# SHIFT_LEFT_RIGHT_1.net
KiCad netlist of a schematic drawn in EAGLE
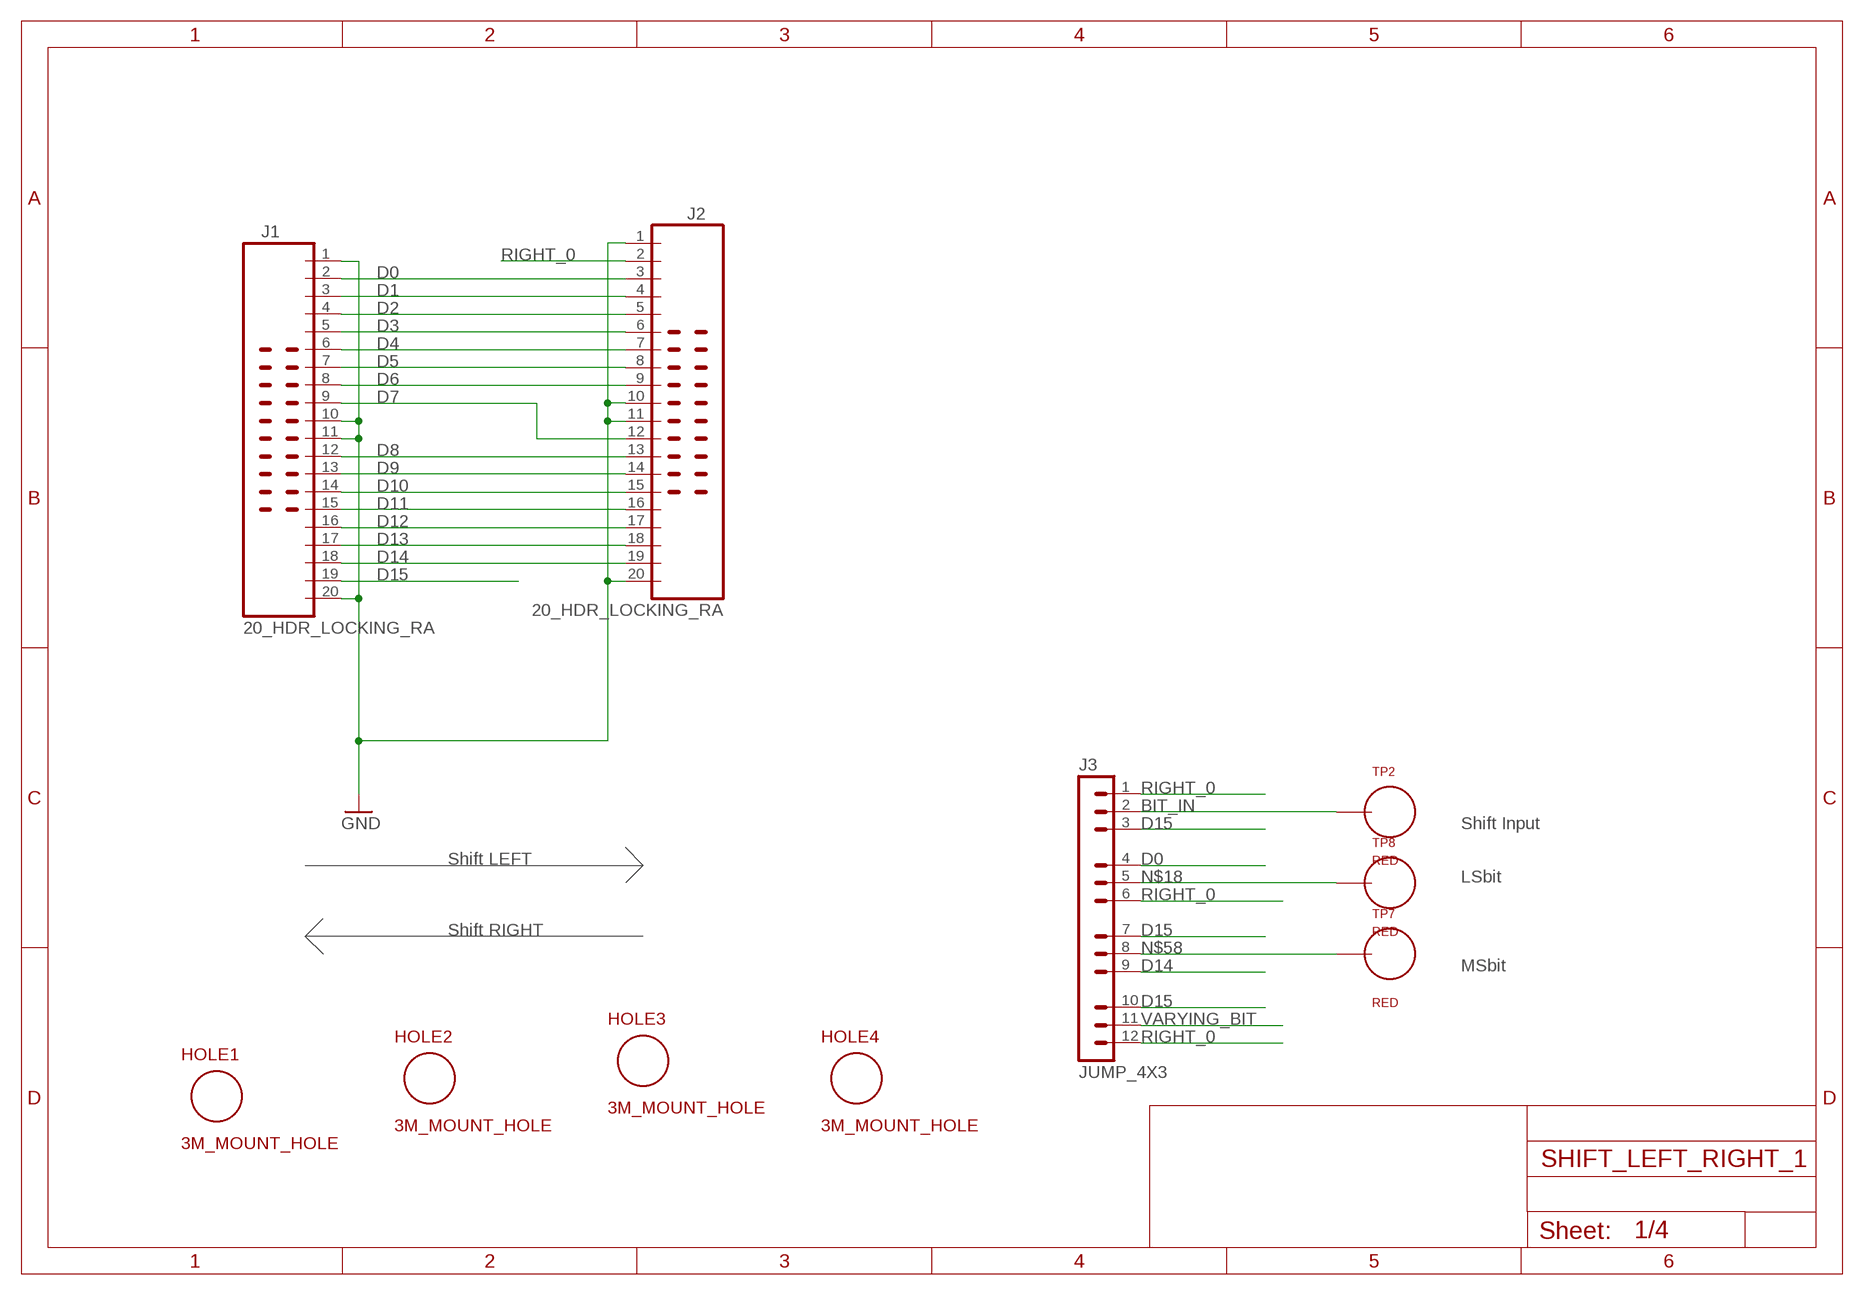
[diagram p0: schematic, sheet 1]
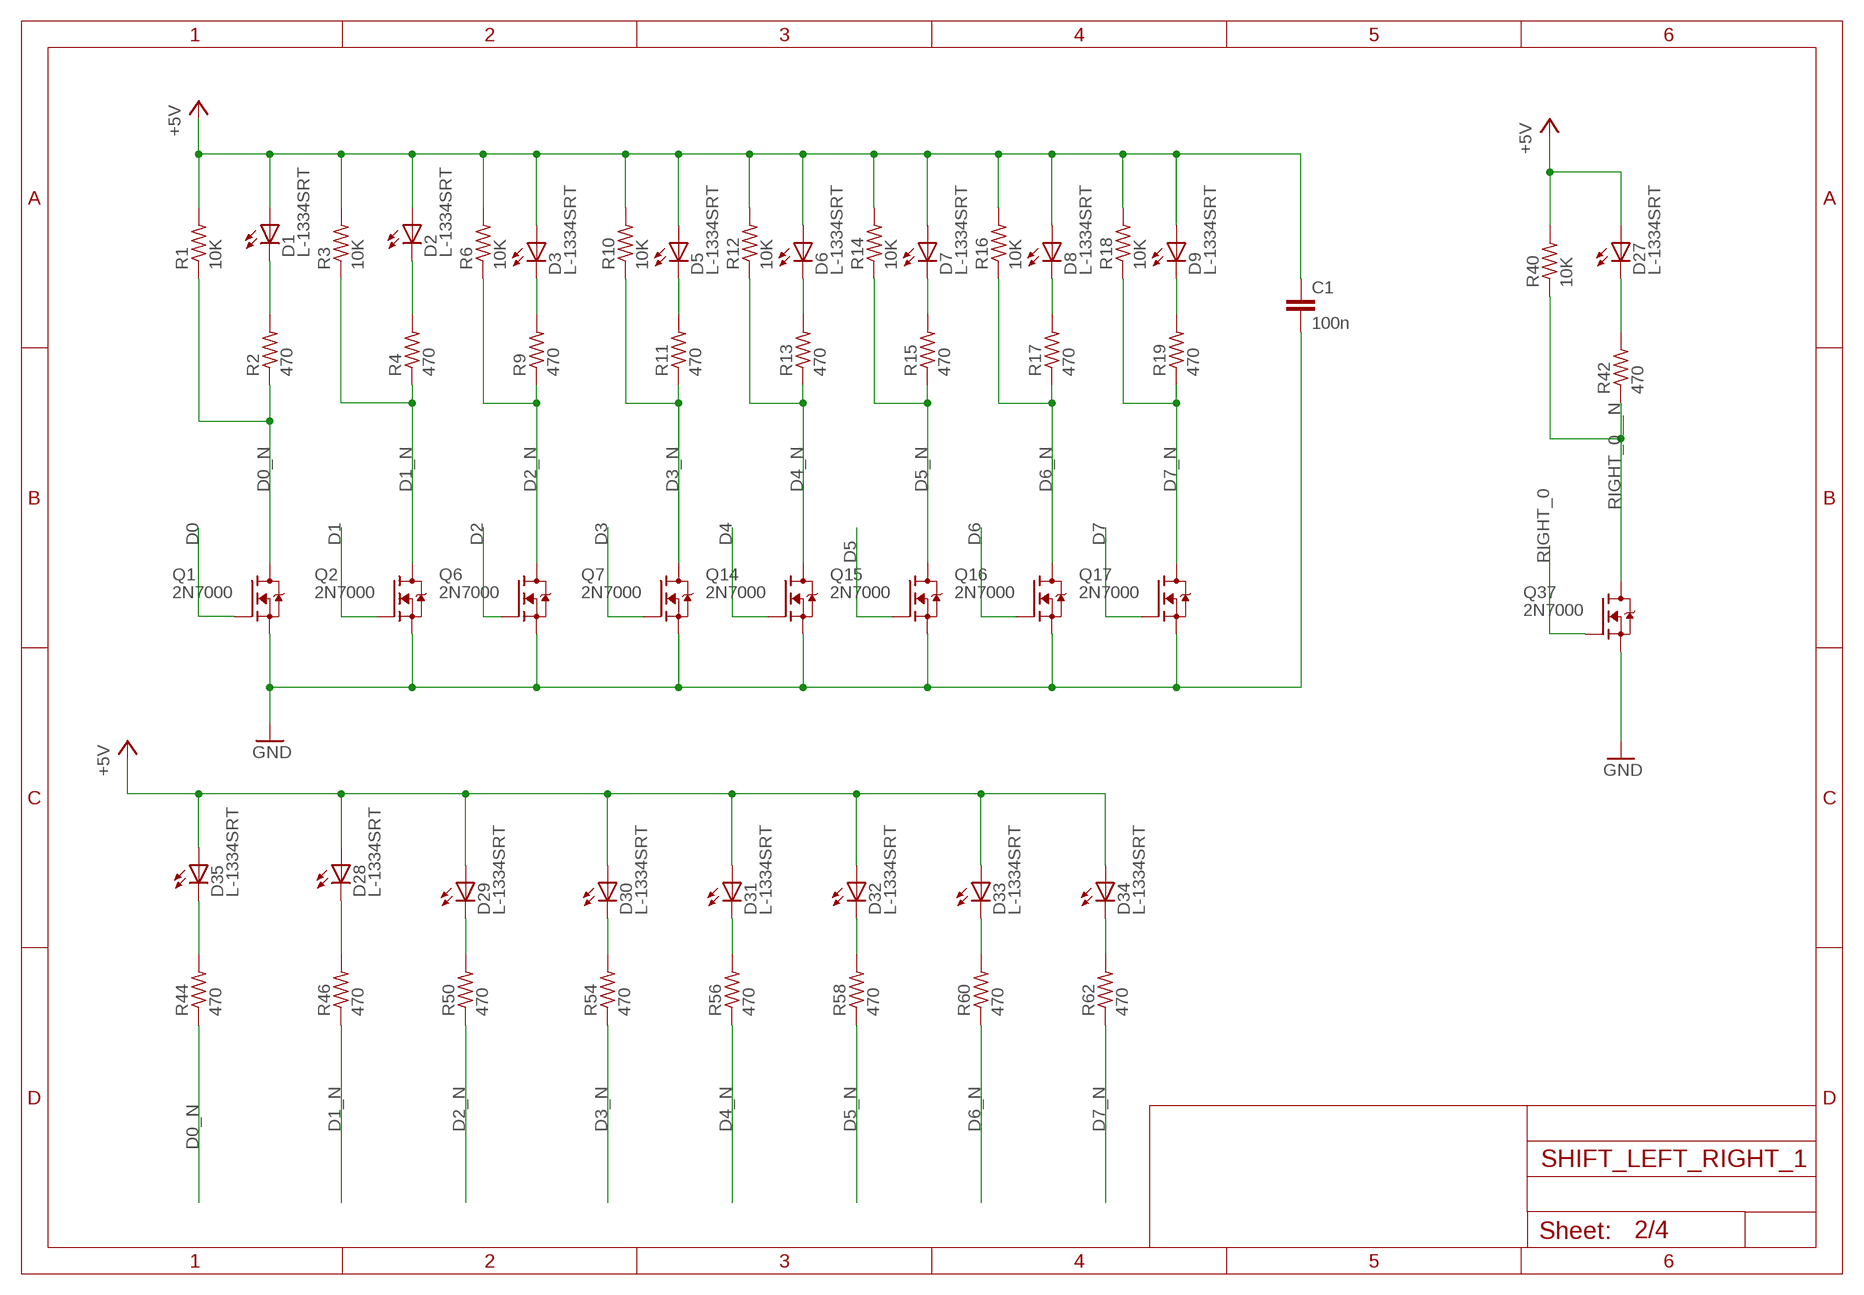
[diagram p1: schematic, sheet 2]
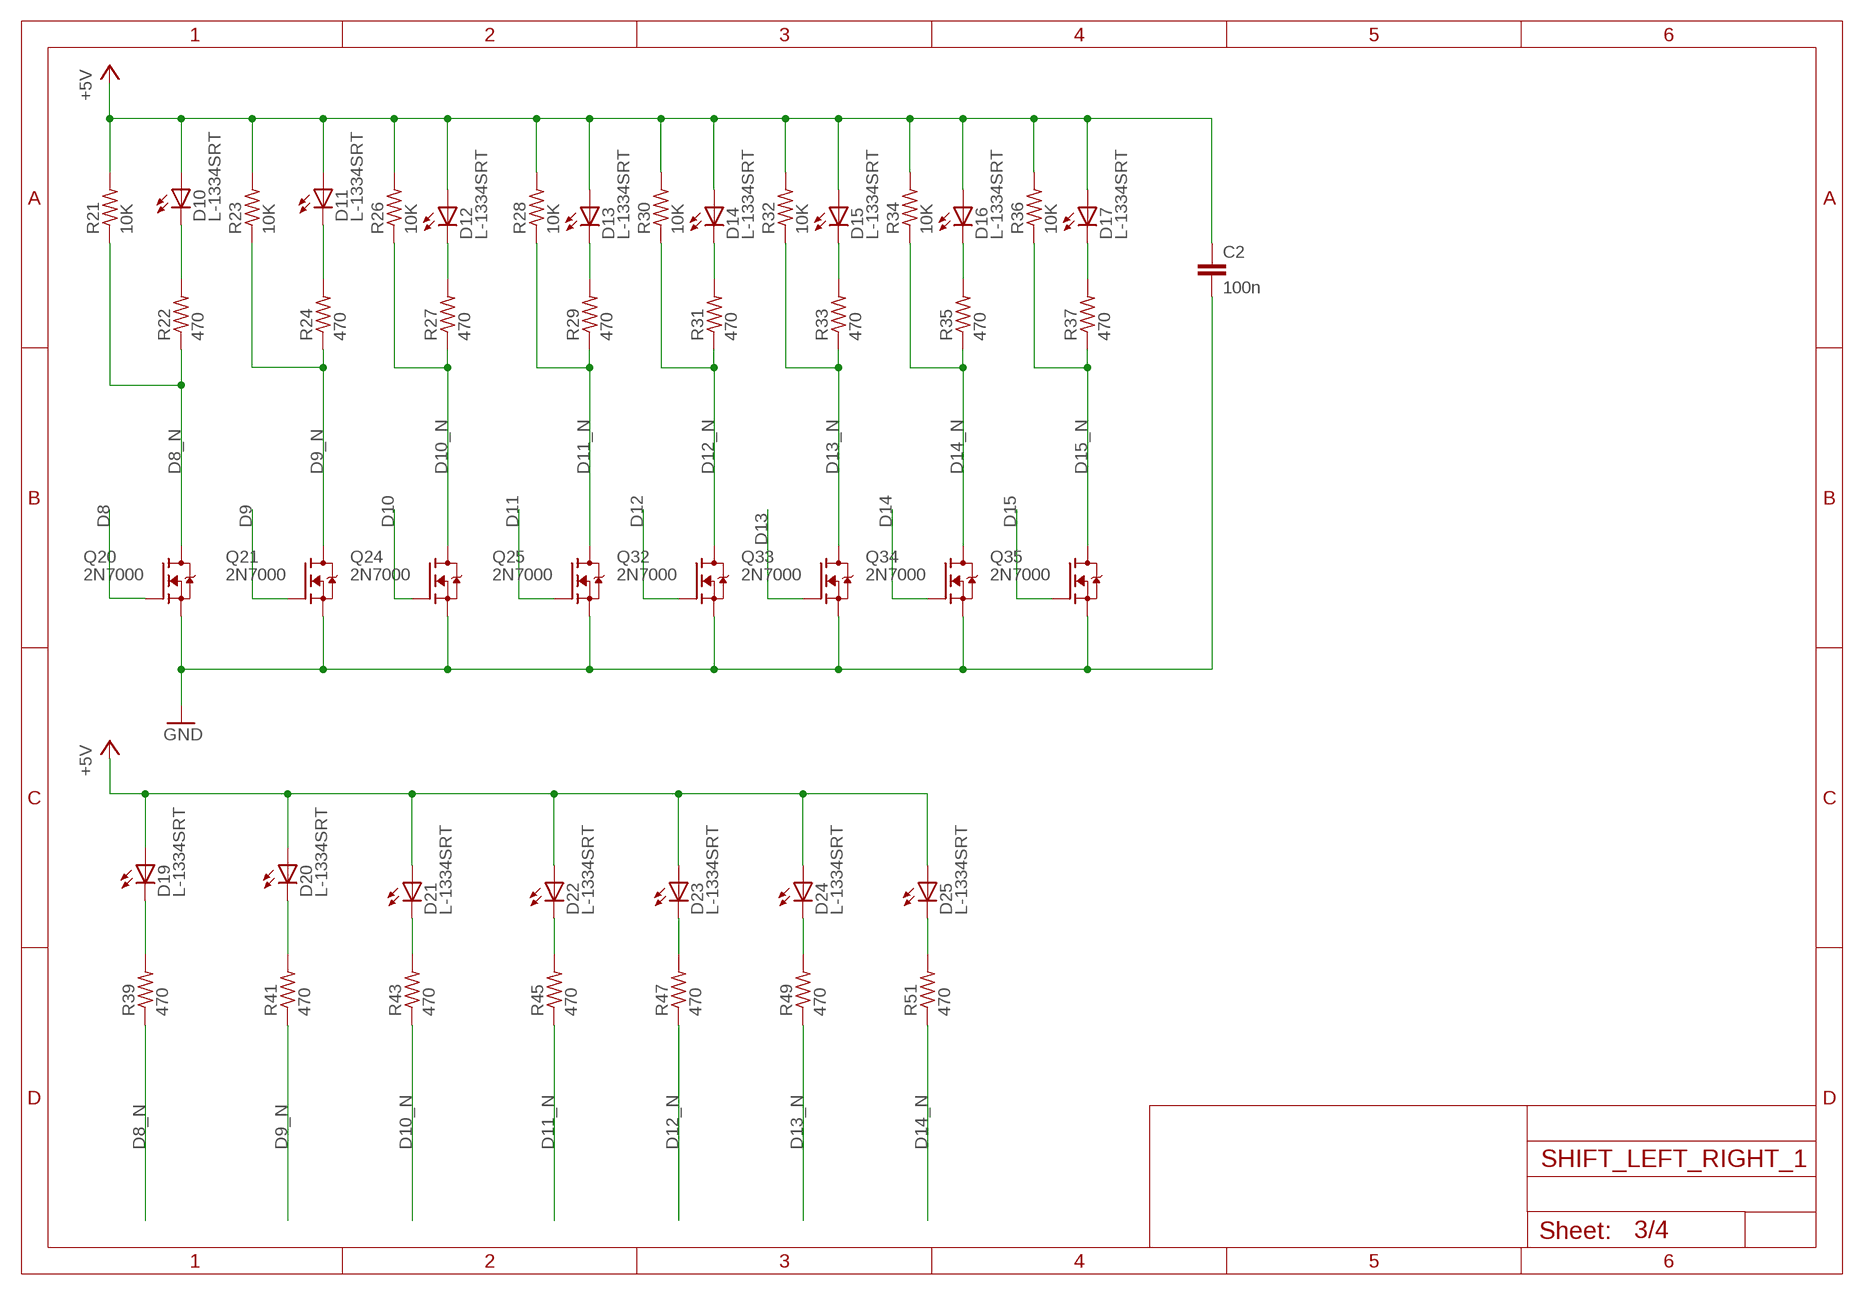
[diagram p2: schematic, sheet 3]
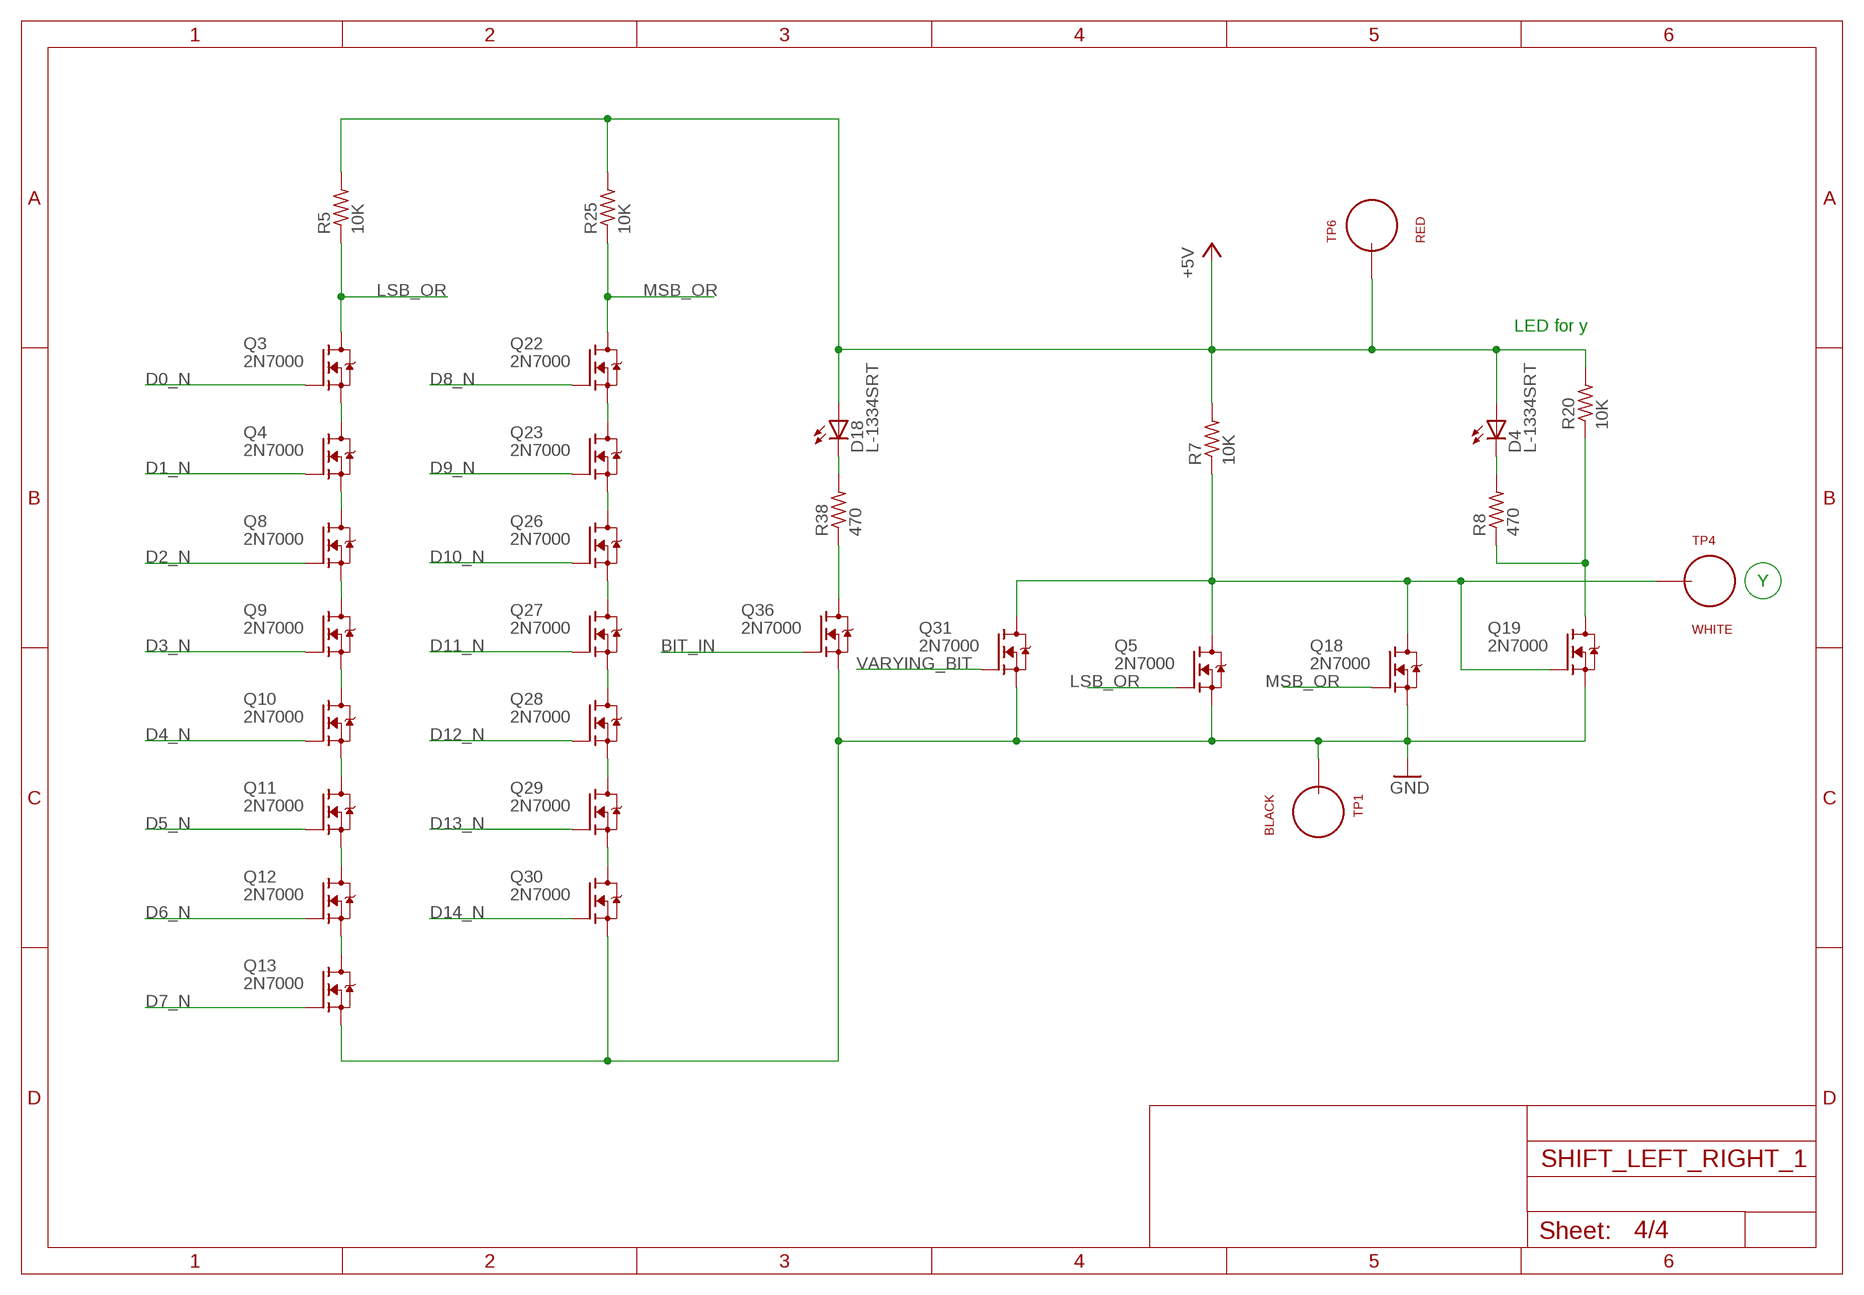
[diagram p3: schematic, sheet 4]

(export (version "E")
  (design (tool "Eeschema 10.0.6"))
  (components
    (comp (ref "C2")
      (value "100n")
      (footprint "eagle-import:CAP_P2INCH")
      (libsource (lib "eagle-import") (part "C_P2INCH"))
    )
    (comp (ref "D10")
      (value "L-1334SRT")
      (footprint "eagle-import:LED3MM")
      (libsource (lib "eagle-import") (part "L-1334SRT"))
    )
    (comp (ref "D11")
      (value "L-1334SRT")
      (footprint "eagle-import:LED3MM")
      (libsource (lib "eagle-import") (part "L-1334SRT"))
    )
    (comp (ref "D12")
      (value "L-1334SRT")
      (footprint "eagle-import:LED3MM")
      (libsource (lib "eagle-import") (part "L-1334SRT"))
    )
    (comp (ref "D13")
      (value "L-1334SRT")
      (footprint "eagle-import:LED3MM")
      (libsource (lib "eagle-import") (part "L-1334SRT"))
    )
    (comp (ref "D14")
      (value "L-1334SRT")
      (footprint "eagle-import:LED3MM")
      (libsource (lib "eagle-import") (part "L-1334SRT"))
    )
    (comp (ref "D15")
      (value "L-1334SRT")
      (footprint "eagle-import:LED3MM")
      (libsource (lib "eagle-import") (part "L-1334SRT"))
    )
    (comp (ref "D16")
      (value "L-1334SRT")
      (footprint "eagle-import:LED3MM")
      (libsource (lib "eagle-import") (part "L-1334SRT"))
    )
    (comp (ref "D17")
      (value "L-1334SRT")
      (footprint "eagle-import:LED3MM")
      (libsource (lib "eagle-import") (part "L-1334SRT"))
    )
    (comp (ref "D19")
      (value "L-1334SRT")
      (footprint "eagle-import:LED3MM")
      (libsource (lib "eagle-import") (part "L-1334SRT"))
    )
    (comp (ref "D20")
      (value "L-1334SRT")
      (footprint "eagle-import:LED3MM")
      (libsource (lib "eagle-import") (part "L-1334SRT"))
    )
    (comp (ref "D21")
      (value "L-1334SRT")
      (footprint "eagle-import:LED3MM")
      (libsource (lib "eagle-import") (part "L-1334SRT"))
    )
    (comp (ref "D22")
      (value "L-1334SRT")
      (footprint "eagle-import:LED3MM")
      (libsource (lib "eagle-import") (part "L-1334SRT"))
    )
    (comp (ref "D23")
      (value "L-1334SRT")
      (footprint "eagle-import:LED3MM")
      (libsource (lib "eagle-import") (part "L-1334SRT"))
    )
    (comp (ref "D24")
      (value "L-1334SRT")
      (footprint "eagle-import:LED3MM")
      (libsource (lib "eagle-import") (part "L-1334SRT"))
    )
    (comp (ref "D25")
      (value "L-1334SRT")
      (footprint "eagle-import:LED3MM")
      (libsource (lib "eagle-import") (part "L-1334SRT"))
    )
    (comp (ref "Q20")
      (value "2N7000")
      (footprint "eagle-import:TO92-DGS")
      (libsource (lib "eagle-import") (part "2N7000"))
    )
    (comp (ref "Q21")
      (value "2N7000")
      (footprint "eagle-import:TO92-DGS")
      (libsource (lib "eagle-import") (part "2N7000"))
    )
    (comp (ref "Q24")
      (value "2N7000")
      (footprint "eagle-import:TO92-DGS")
      (libsource (lib "eagle-import") (part "2N7000"))
    )
    (comp (ref "Q25")
      (value "2N7000")
      (footprint "eagle-import:TO92-DGS")
      (libsource (lib "eagle-import") (part "2N7000"))
    )
    (comp (ref "Q32")
      (value "2N7000")
      (footprint "eagle-import:TO92-DGS")
      (libsource (lib "eagle-import") (part "2N7000"))
    )
    (comp (ref "Q33")
      (value "2N7000")
      (footprint "eagle-import:TO92-DGS")
      (libsource (lib "eagle-import") (part "2N7000"))
    )
    (comp (ref "Q34")
      (value "2N7000")
      (footprint "eagle-import:TO92-DGS")
      (libsource (lib "eagle-import") (part "2N7000"))
    )
    (comp (ref "Q35")
      (value "2N7000")
      (footprint "eagle-import:TO92-DGS")
      (libsource (lib "eagle-import") (part "2N7000"))
    )
    (comp (ref "R21")
      (value "10K")
      (footprint "eagle-import:R_P2INCH")
      (libsource (lib "eagle-import") (part "R_P2INCH"))
    )
    (comp (ref "R22")
      (value "470")
      (footprint "eagle-import:R_P2INCH")
      (libsource (lib "eagle-import") (part "R_P2INCH"))
    )
    (comp (ref "R23")
      (value "10K")
      (footprint "eagle-import:R_P2INCH")
      (libsource (lib "eagle-import") (part "R_P2INCH"))
    )
    (comp (ref "R24")
      (value "470")
      (footprint "eagle-import:R_P2INCH")
      (libsource (lib "eagle-import") (part "R_P2INCH"))
    )
    (comp (ref "R26")
      (value "10K")
      (footprint "eagle-import:R_P2INCH")
      (libsource (lib "eagle-import") (part "R_P2INCH"))
    )
    (comp (ref "R27")
      (value "470")
      (footprint "eagle-import:R_P2INCH")
      (libsource (lib "eagle-import") (part "R_P2INCH"))
    )
    (comp (ref "R28")
      (value "10K")
      (footprint "eagle-import:R_P2INCH")
      (libsource (lib "eagle-import") (part "R_P2INCH"))
    )
    (comp (ref "R29")
      (value "470")
      (footprint "eagle-import:R_P2INCH")
      (libsource (lib "eagle-import") (part "R_P2INCH"))
    )
    (comp (ref "R30")
      (value "10K")
      (footprint "eagle-import:R_P2INCH")
      (libsource (lib "eagle-import") (part "R_P2INCH"))
    )
    (comp (ref "R31")
      (value "470")
      (footprint "eagle-import:R_P2INCH")
      (libsource (lib "eagle-import") (part "R_P2INCH"))
    )
    (comp (ref "R32")
      (value "10K")
      (footprint "eagle-import:R_P2INCH")
      (libsource (lib "eagle-import") (part "R_P2INCH"))
    )
    (comp (ref "R33")
      (value "470")
      (footprint "eagle-import:R_P2INCH")
      (libsource (lib "eagle-import") (part "R_P2INCH"))
    )
    (comp (ref "R34")
      (value "10K")
      (footprint "eagle-import:R_P2INCH")
      (libsource (lib "eagle-import") (part "R_P2INCH"))
    )
    (comp (ref "R35")
      (value "470")
      (footprint "eagle-import:R_P2INCH")
      (libsource (lib "eagle-import") (part "R_P2INCH"))
    )
    (comp (ref "R36")
      (value "10K")
      (footprint "eagle-import:R_P2INCH")
      (libsource (lib "eagle-import") (part "R_P2INCH"))
    )
    (comp (ref "R37")
      (value "470")
      (footprint "eagle-import:R_P2INCH")
      (libsource (lib "eagle-import") (part "R_P2INCH"))
    )
    (comp (ref "R39")
      (value "470")
      (footprint "eagle-import:R_P2INCH")
      (libsource (lib "eagle-import") (part "R_P2INCH"))
    )
    (comp (ref "R41")
      (value "470")
      (footprint "eagle-import:R_P2INCH")
      (libsource (lib "eagle-import") (part "R_P2INCH"))
    )
    (comp (ref "R43")
      (value "470")
      (footprint "eagle-import:R_P2INCH")
      (libsource (lib "eagle-import") (part "R_P2INCH"))
    )
    (comp (ref "R45")
      (value "470")
      (footprint "eagle-import:R_P2INCH")
      (libsource (lib "eagle-import") (part "R_P2INCH"))
    )
    (comp (ref "R47")
      (value "470")
      (footprint "eagle-import:R_P2INCH")
      (libsource (lib "eagle-import") (part "R_P2INCH"))
    )
    (comp (ref "R49")
      (value "470")
      (footprint "eagle-import:R_P2INCH")
      (libsource (lib "eagle-import") (part "R_P2INCH"))
    )
    (comp (ref "R51")
      (value "470")
      (footprint "eagle-import:R_P2INCH")
      (libsource (lib "eagle-import") (part "R_P2INCH"))
    )
    (comp (ref "C1")
      (value "100n")
      (footprint "eagle-import:CAP_P2INCH")
      (libsource (lib "eagle-import") (part "C_P2INCH"))
    )
    (comp (ref "D1")
      (value "L-1334SRT")
      (footprint "eagle-import:LED3MM")
      (libsource (lib "eagle-import") (part "L-1334SRT"))
    )
    (comp (ref "D2")
      (value "L-1334SRT")
      (footprint "eagle-import:LED3MM")
      (libsource (lib "eagle-import") (part "L-1334SRT"))
    )
    (comp (ref "D3")
      (value "L-1334SRT")
      (footprint "eagle-import:LED3MM")
      (libsource (lib "eagle-import") (part "L-1334SRT"))
    )
    (comp (ref "D5")
      (value "L-1334SRT")
      (footprint "eagle-import:LED3MM")
      (libsource (lib "eagle-import") (part "L-1334SRT"))
    )
    (comp (ref "D6")
      (value "L-1334SRT")
      (footprint "eagle-import:LED3MM")
      (libsource (lib "eagle-import") (part "L-1334SRT"))
    )
    (comp (ref "D7")
      (value "L-1334SRT")
      (footprint "eagle-import:LED3MM")
      (libsource (lib "eagle-import") (part "L-1334SRT"))
    )
    (comp (ref "D8")
      (value "L-1334SRT")
      (footprint "eagle-import:LED3MM")
      (libsource (lib "eagle-import") (part "L-1334SRT"))
    )
    (comp (ref "D9")
      (value "L-1334SRT")
      (footprint "eagle-import:LED3MM")
      (libsource (lib "eagle-import") (part "L-1334SRT"))
    )
    (comp (ref "D27")
      (value "L-1334SRT")
      (footprint "eagle-import:LED3MM")
      (libsource (lib "eagle-import") (part "L-1334SRT"))
    )
    (comp (ref "D28")
      (value "L-1334SRT")
      (footprint "eagle-import:LED3MM")
      (libsource (lib "eagle-import") (part "L-1334SRT"))
    )
    (comp (ref "D29")
      (value "L-1334SRT")
      (footprint "eagle-import:LED3MM")
      (libsource (lib "eagle-import") (part "L-1334SRT"))
    )
    (comp (ref "D30")
      (value "L-1334SRT")
      (footprint "eagle-import:LED3MM")
      (libsource (lib "eagle-import") (part "L-1334SRT"))
    )
    (comp (ref "D31")
      (value "L-1334SRT")
      (footprint "eagle-import:LED3MM")
      (libsource (lib "eagle-import") (part "L-1334SRT"))
    )
    (comp (ref "D32")
      (value "L-1334SRT")
      (footprint "eagle-import:LED3MM")
      (libsource (lib "eagle-import") (part "L-1334SRT"))
    )
    (comp (ref "D33")
      (value "L-1334SRT")
      (footprint "eagle-import:LED3MM")
      (libsource (lib "eagle-import") (part "L-1334SRT"))
    )
    (comp (ref "D34")
      (value "L-1334SRT")
      (footprint "eagle-import:LED3MM")
      (libsource (lib "eagle-import") (part "L-1334SRT"))
    )
    (comp (ref "D35")
      (value "L-1334SRT")
      (footprint "eagle-import:LED3MM")
      (libsource (lib "eagle-import") (part "L-1334SRT"))
    )
    (comp (ref "Q1")
      (value "2N7000")
      (footprint "eagle-import:TO92-DGS")
      (libsource (lib "eagle-import") (part "2N7000"))
    )
    (comp (ref "Q2")
      (value "2N7000")
      (footprint "eagle-import:TO92-DGS")
      (libsource (lib "eagle-import") (part "2N7000"))
    )
    (comp (ref "Q6")
      (value "2N7000")
      (footprint "eagle-import:TO92-DGS")
      (libsource (lib "eagle-import") (part "2N7000"))
    )
    (comp (ref "Q7")
      (value "2N7000")
      (footprint "eagle-import:TO92-DGS")
      (libsource (lib "eagle-import") (part "2N7000"))
    )
    (comp (ref "Q14")
      (value "2N7000")
      (footprint "eagle-import:TO92-DGS")
      (libsource (lib "eagle-import") (part "2N7000"))
    )
    (comp (ref "Q15")
      (value "2N7000")
      (footprint "eagle-import:TO92-DGS")
      (libsource (lib "eagle-import") (part "2N7000"))
    )
    (comp (ref "Q16")
      (value "2N7000")
      (footprint "eagle-import:TO92-DGS")
      (libsource (lib "eagle-import") (part "2N7000"))
    )
    (comp (ref "Q17")
      (value "2N7000")
      (footprint "eagle-import:TO92-DGS")
      (libsource (lib "eagle-import") (part "2N7000"))
    )
    (comp (ref "Q37")
      (value "2N7000")
      (footprint "eagle-import:TO92-DGS")
      (libsource (lib "eagle-import") (part "2N7000"))
    )
    (comp (ref "R1")
      (value "10K")
      (footprint "eagle-import:R_P2INCH")
      (libsource (lib "eagle-import") (part "R_P2INCH"))
    )
    (comp (ref "R2")
      (value "470")
      (footprint "eagle-import:R_P2INCH")
      (libsource (lib "eagle-import") (part "R_P2INCH"))
    )
    (comp (ref "R3")
      (value "10K")
      (footprint "eagle-import:R_P2INCH")
      (libsource (lib "eagle-import") (part "R_P2INCH"))
    )
    (comp (ref "R4")
      (value "470")
      (footprint "eagle-import:R_P2INCH")
      (libsource (lib "eagle-import") (part "R_P2INCH"))
    )
    (comp (ref "R6")
      (value "10K")
      (footprint "eagle-import:R_P2INCH")
      (libsource (lib "eagle-import") (part "R_P2INCH"))
    )
    (comp (ref "R9")
      (value "470")
      (footprint "eagle-import:R_P2INCH")
      (libsource (lib "eagle-import") (part "R_P2INCH"))
    )
    (comp (ref "R10")
      (value "10K")
      (footprint "eagle-import:R_P2INCH")
      (libsource (lib "eagle-import") (part "R_P2INCH"))
    )
    (comp (ref "R11")
      (value "470")
      (footprint "eagle-import:R_P2INCH")
      (libsource (lib "eagle-import") (part "R_P2INCH"))
    )
    (comp (ref "R12")
      (value "10K")
      (footprint "eagle-import:R_P2INCH")
      (libsource (lib "eagle-import") (part "R_P2INCH"))
    )
    (comp (ref "R13")
      (value "470")
      (footprint "eagle-import:R_P2INCH")
      (libsource (lib "eagle-import") (part "R_P2INCH"))
    )
    (comp (ref "R14")
      (value "10K")
      (footprint "eagle-import:R_P2INCH")
      (libsource (lib "eagle-import") (part "R_P2INCH"))
    )
    (comp (ref "R15")
      (value "470")
      (footprint "eagle-import:R_P2INCH")
      (libsource (lib "eagle-import") (part "R_P2INCH"))
    )
    (comp (ref "R16")
      (value "10K")
      (footprint "eagle-import:R_P2INCH")
      (libsource (lib "eagle-import") (part "R_P2INCH"))
    )
    (comp (ref "R17")
      (value "470")
      (footprint "eagle-import:R_P2INCH")
      (libsource (lib "eagle-import") (part "R_P2INCH"))
    )
    (comp (ref "R18")
      (value "10K")
      (footprint "eagle-import:R_P2INCH")
      (libsource (lib "eagle-import") (part "R_P2INCH"))
    )
    (comp (ref "R19")
      (value "470")
      (footprint "eagle-import:R_P2INCH")
      (libsource (lib "eagle-import") (part "R_P2INCH"))
    )
    (comp (ref "R40")
      (value "10K")
      (footprint "eagle-import:R_P2INCH")
      (libsource (lib "eagle-import") (part "R_P2INCH"))
    )
    (comp (ref "R42")
      (value "470")
      (footprint "eagle-import:R_P2INCH")
      (libsource (lib "eagle-import") (part "R_P2INCH"))
    )
    (comp (ref "R44")
      (value "470")
      (footprint "eagle-import:R_P2INCH")
      (libsource (lib "eagle-import") (part "R_P2INCH"))
    )
    (comp (ref "R46")
      (value "470")
      (footprint "eagle-import:R_P2INCH")
      (libsource (lib "eagle-import") (part "R_P2INCH"))
    )
    (comp (ref "R50")
      (value "470")
      (footprint "eagle-import:R_P2INCH")
      (libsource (lib "eagle-import") (part "R_P2INCH"))
    )
    (comp (ref "R54")
      (value "470")
      (footprint "eagle-import:R_P2INCH")
      (libsource (lib "eagle-import") (part "R_P2INCH"))
    )
    (comp (ref "R56")
      (value "470")
      (footprint "eagle-import:R_P2INCH")
      (libsource (lib "eagle-import") (part "R_P2INCH"))
    )
    (comp (ref "R58")
      (value "470")
      (footprint "eagle-import:R_P2INCH")
      (libsource (lib "eagle-import") (part "R_P2INCH"))
    )
    (comp (ref "R60")
      (value "470")
      (footprint "eagle-import:R_P2INCH")
      (libsource (lib "eagle-import") (part "R_P2INCH"))
    )
    (comp (ref "R62")
      (value "470")
      (footprint "eagle-import:R_P2INCH")
      (libsource (lib "eagle-import") (part "R_P2INCH"))
    )
    (comp (ref "D4")
      (value "L-1334SRT")
      (footprint "eagle-import:LED3MM")
      (libsource (lib "eagle-import") (part "L-1334SRT"))
    )
    (comp (ref "D18")
      (value "L-1334SRT")
      (footprint "eagle-import:LED3MM")
      (libsource (lib "eagle-import") (part "L-1334SRT"))
    )
    (comp (ref "Q3")
      (value "2N7000")
      (footprint "eagle-import:TO92-DGS")
      (libsource (lib "eagle-import") (part "2N7000"))
    )
    (comp (ref "Q4")
      (value "2N7000")
      (footprint "eagle-import:TO92-DGS")
      (libsource (lib "eagle-import") (part "2N7000"))
    )
    (comp (ref "Q5")
      (value "2N7000")
      (footprint "eagle-import:TO92-DGS")
      (libsource (lib "eagle-import") (part "2N7000"))
    )
    (comp (ref "Q8")
      (value "2N7000")
      (footprint "eagle-import:TO92-DGS")
      (libsource (lib "eagle-import") (part "2N7000"))
    )
    (comp (ref "Q9")
      (value "2N7000")
      (footprint "eagle-import:TO92-DGS")
      (libsource (lib "eagle-import") (part "2N7000"))
    )
    (comp (ref "Q10")
      (value "2N7000")
      (footprint "eagle-import:TO92-DGS")
      (libsource (lib "eagle-import") (part "2N7000"))
    )
    (comp (ref "Q11")
      (value "2N7000")
      (footprint "eagle-import:TO92-DGS")
      (libsource (lib "eagle-import") (part "2N7000"))
    )
    (comp (ref "Q12")
      (value "2N7000")
      (footprint "eagle-import:TO92-DGS")
      (libsource (lib "eagle-import") (part "2N7000"))
    )
    (comp (ref "Q13")
      (value "2N7000")
      (footprint "eagle-import:TO92-DGS")
      (libsource (lib "eagle-import") (part "2N7000"))
    )
    (comp (ref "Q18")
      (value "2N7000")
      (footprint "eagle-import:TO92-DGS")
      (libsource (lib "eagle-import") (part "2N7000"))
    )
    (comp (ref "Q19")
      (value "2N7000")
      (footprint "eagle-import:TO92-DGS")
      (libsource (lib "eagle-import") (part "2N7000"))
    )
    (comp (ref "Q22")
      (value "2N7000")
      (footprint "eagle-import:TO92-DGS")
      (libsource (lib "eagle-import") (part "2N7000"))
    )
    (comp (ref "Q23")
      (value "2N7000")
      (footprint "eagle-import:TO92-DGS")
      (libsource (lib "eagle-import") (part "2N7000"))
    )
    (comp (ref "Q26")
      (value "2N7000")
      (footprint "eagle-import:TO92-DGS")
      (libsource (lib "eagle-import") (part "2N7000"))
    )
    (comp (ref "Q27")
      (value "2N7000")
      (footprint "eagle-import:TO92-DGS")
      (libsource (lib "eagle-import") (part "2N7000"))
    )
    (comp (ref "Q28")
      (value "2N7000")
      (footprint "eagle-import:TO92-DGS")
      (libsource (lib "eagle-import") (part "2N7000"))
    )
    (comp (ref "Q29")
      (value "2N7000")
      (footprint "eagle-import:TO92-DGS")
      (libsource (lib "eagle-import") (part "2N7000"))
    )
    (comp (ref "Q30")
      (value "2N7000")
      (footprint "eagle-import:TO92-DGS")
      (libsource (lib "eagle-import") (part "2N7000"))
    )
    (comp (ref "Q31")
      (value "2N7000")
      (footprint "eagle-import:TO92-DGS")
      (libsource (lib "eagle-import") (part "2N7000"))
    )
    (comp (ref "Q36")
      (value "2N7000")
      (footprint "eagle-import:TO92-DGS")
      (libsource (lib "eagle-import") (part "2N7000"))
    )
    (comp (ref "R5")
      (value "10K")
      (footprint "eagle-import:R_P2INCH")
      (libsource (lib "eagle-import") (part "R_P2INCH"))
    )
    (comp (ref "R7")
      (value "10K")
      (footprint "eagle-import:R_P2INCH")
      (libsource (lib "eagle-import") (part "R_P2INCH"))
    )
    (comp (ref "R8")
      (value "470")
      (footprint "eagle-import:R_P2INCH")
      (libsource (lib "eagle-import") (part "R_P2INCH"))
    )
    (comp (ref "R20")
      (value "10K")
      (footprint "eagle-import:R_P2INCH")
      (libsource (lib "eagle-import") (part "R_P2INCH"))
    )
    (comp (ref "R25")
      (value "10K")
      (footprint "eagle-import:R_P2INCH")
      (libsource (lib "eagle-import") (part "R_P2INCH"))
    )
    (comp (ref "R38")
      (value "470")
      (footprint "eagle-import:R_P2INCH")
      (libsource (lib "eagle-import") (part "R_P2INCH"))
    )
    (comp (ref "TP1")
      (value "BLACK")
      (footprint "eagle-import:TEST_LOOP")
      (libsource (lib "eagle-import") (part "TEST_LOOP"))
    )
    (comp (ref "TP4")
      (value "WHITE")
      (footprint "eagle-import:TEST_LOOP")
      (libsource (lib "eagle-import") (part "TEST_LOOP"))
    )
    (comp (ref "TP6")
      (value "RED")
      (footprint "eagle-import:TEST_LOOP")
      (libsource (lib "eagle-import") (part "TEST_LOOP"))
    )
    (comp (ref "HOLE1")
      (value "3M_MOUNT_HOLE")
      (footprint "eagle-import:3M_HOLE")
      (libsource (lib "eagle-import") (part "3M_MOUNT_HOLE"))
    )
    (comp (ref "HOLE2")
      (value "3M_MOUNT_HOLE")
      (footprint "eagle-import:3M_HOLE")
      (libsource (lib "eagle-import") (part "3M_MOUNT_HOLE"))
    )
    (comp (ref "HOLE3")
      (value "3M_MOUNT_HOLE")
      (footprint "eagle-import:3M_HOLE")
      (libsource (lib "eagle-import") (part "3M_MOUNT_HOLE"))
    )
    (comp (ref "HOLE4")
      (value "3M_MOUNT_HOLE")
      (footprint "eagle-import:3M_HOLE")
      (libsource (lib "eagle-import") (part "3M_MOUNT_HOLE"))
    )
    (comp (ref "J1")
      (value "20_HDR_LOCKING_RA")
      (footprint "eagle-import:20_HDR_LOCKING_RA")
      (libsource (lib "eagle-import") (part "20_HDR_LOCKING_RA"))
    )
    (comp (ref "J2")
      (value "20_HDR_LOCKING_RA")
      (footprint "eagle-import:20_HDR_LOCKING_RA")
      (libsource (lib "eagle-import") (part "20_HDR_LOCKING_RA"))
    )
    (comp (ref "J3")
      (value "JUMP_4X3")
      (footprint "eagle-import:JUMP_4X3")
      (libsource (lib "eagle-import") (part "JUMP_4X3"))
    )
    (comp (ref "TP2")
      (value "RED")
      (footprint "eagle-import:TEST_LOOP")
      (libsource (lib "eagle-import") (part "TEST_LOOP"))
    )
    (comp (ref "TP7")
      (value "RED")
      (footprint "eagle-import:TEST_LOOP")
      (libsource (lib "eagle-import") (part "TEST_LOOP"))
    )
    (comp (ref "TP8")
      (value "RED")
      (footprint "eagle-import:TEST_LOOP")
      (libsource (lib "eagle-import") (part "TEST_LOOP"))
    )
  )
  (nets
    (net (code "1") (name "+5V") (class "Default")
      (node (ref "C1") (pin "1") (pinfunction "1_1") (pintype "passive"))
      (node (ref "C2") (pin "1") (pinfunction "1_1") (pintype "passive"))
      (node (ref "D1") (pin "A") (pinfunction "A_A") (pintype "passive"))
      (node (ref "D10") (pin "A") (pinfunction "A_A") (pintype "passive"))
      (node (ref "D11") (pin "A") (pinfunction "A_A") (pintype "passive"))
      (node (ref "D12") (pin "A") (pinfunction "A_A") (pintype "passive"))
      (node (ref "D13") (pin "A") (pinfunction "A_A") (pintype "passive"))
      (node (ref "D14") (pin "A") (pinfunction "A_A") (pintype "passive"))
      (node (ref "D15") (pin "A") (pinfunction "A_A") (pintype "passive"))
      (node (ref "D16") (pin "A") (pinfunction "A_A") (pintype "passive"))
      (node (ref "D17") (pin "A") (pinfunction "A_A") (pintype "passive"))
      (node (ref "D18") (pin "A") (pinfunction "A_A") (pintype "passive"))
      (node (ref "D19") (pin "A") (pinfunction "A_A") (pintype "passive"))
      (node (ref "D2") (pin "A") (pinfunction "A_A") (pintype "passive"))
      (node (ref "D20") (pin "A") (pinfunction "A_A") (pintype "passive"))
      (node (ref "D21") (pin "A") (pinfunction "A_A") (pintype "passive"))
      (node (ref "D22") (pin "A") (pinfunction "A_A") (pintype "passive"))
      (node (ref "D23") (pin "A") (pinfunction "A_A") (pintype "passive"))
      (node (ref "D24") (pin "A") (pinfunction "A_A") (pintype "passive"))
      (node (ref "D25") (pin "A") (pinfunction "A_A") (pintype "passive"))
      (node (ref "D27") (pin "A") (pinfunction "A_A") (pintype "passive"))
      (node (ref "D28") (pin "A") (pinfunction "A_A") (pintype "passive"))
      (node (ref "D29") (pin "A") (pinfunction "A_A") (pintype "passive"))
      (node (ref "D3") (pin "A") (pinfunction "A_A") (pintype "passive"))
      (node (ref "D30") (pin "A") (pinfunction "A_A") (pintype "passive"))
      (node (ref "D31") (pin "A") (pinfunction "A_A") (pintype "passive"))
      (node (ref "D32") (pin "A") (pinfunction "A_A") (pintype "passive"))
      (node (ref "D33") (pin "A") (pinfunction "A_A") (pintype "passive"))
      (node (ref "D34") (pin "A") (pinfunction "A_A") (pintype "passive"))
      (node (ref "D35") (pin "A") (pinfunction "A_A") (pintype "passive"))
      (node (ref "D4") (pin "A") (pinfunction "A_A") (pintype "passive"))
      (node (ref "D5") (pin "A") (pinfunction "A_A") (pintype "passive"))
      (node (ref "D6") (pin "A") (pinfunction "A_A") (pintype "passive"))
      (node (ref "D7") (pin "A") (pinfunction "A_A") (pintype "passive"))
      (node (ref "D8") (pin "A") (pinfunction "A_A") (pintype "passive"))
      (node (ref "D9") (pin "A") (pinfunction "A_A") (pintype "passive"))
      (node (ref "R1") (pin "2") (pinfunction "2_2") (pintype "passive"))
      (node (ref "R10") (pin "2") (pinfunction "2_2") (pintype "passive"))
      (node (ref "R12") (pin "2") (pinfunction "2_2") (pintype "passive"))
      (node (ref "R14") (pin "2") (pinfunction "2_2") (pintype "passive"))
      (node (ref "R16") (pin "2") (pinfunction "2_2") (pintype "passive"))
      (node (ref "R18") (pin "2") (pinfunction "2_2") (pintype "passive"))
      (node (ref "R20") (pin "2") (pinfunction "2_2") (pintype "passive"))
      (node (ref "R21") (pin "2") (pinfunction "2_2") (pintype "passive"))
      (node (ref "R23") (pin "2") (pinfunction "2_2") (pintype "passive"))
      (node (ref "R25") (pin "2") (pinfunction "2_2") (pintype "passive"))
      (node (ref "R26") (pin "2") (pinfunction "2_2") (pintype "passive"))
      (node (ref "R28") (pin "2") (pinfunction "2_2") (pintype "passive"))
      (node (ref "R3") (pin "2") (pinfunction "2_2") (pintype "passive"))
      (node (ref "R30") (pin "2") (pinfunction "2_2") (pintype "passive"))
      (node (ref "R32") (pin "2") (pinfunction "2_2") (pintype "passive"))
      (node (ref "R34") (pin "2") (pinfunction "2_2") (pintype "passive"))
      (node (ref "R36") (pin "2") (pinfunction "2_2") (pintype "passive"))
      (node (ref "R40") (pin "2") (pinfunction "2_2") (pintype "passive"))
      (node (ref "R5") (pin "2") (pinfunction "2_2") (pintype "passive"))
      (node (ref "R6") (pin "2") (pinfunction "2_2") (pintype "passive"))
      (node (ref "R7") (pin "2") (pinfunction "2_2") (pintype "passive"))
      (node (ref "TP6") (pin "P$1") (pinfunction "P$1_P$1") (pintype "bidirectional"))
    )
    (net (code "2") (name "BIT_IN") (class "Default")
      (node (ref "J3") (pin "2") (pinfunction "2_2") (pintype "passive"))
      (node (ref "Q36") (pin "G") (pinfunction "G_G") (pintype "passive"))
      (node (ref "TP2") (pin "P$1") (pinfunction "P$1_P$1") (pintype "bidirectional"))
    )
    (net (code "3") (name "D0") (class "Default")
      (node (ref "J1") (pin "2") (pinfunction "2_2") (pintype "bidirectional"))
      (node (ref "J2") (pin "3") (pinfunction "3_3") (pintype "bidirectional"))
      (node (ref "J3") (pin "4") (pinfunction "4_4") (pintype "passive"))
      (node (ref "Q1") (pin "G") (pinfunction "G_G") (pintype "passive"))
    )
    (net (code "4") (name "D0_N") (class "Default")
      (node (ref "Q1") (pin "D") (pinfunction "D_D") (pintype "passive"))
      (node (ref "Q3") (pin "G") (pinfunction "G_G") (pintype "passive"))
      (node (ref "R1") (pin "1") (pinfunction "1_1") (pintype "passive"))
      (node (ref "R2") (pin "1") (pinfunction "1_1") (pintype "passive"))
      (node (ref "R44") (pin "1") (pinfunction "1_1") (pintype "passive"))
    )
    (net (code "5") (name "D1") (class "Default")
      (node (ref "J1") (pin "3") (pinfunction "3_3") (pintype "bidirectional"))
      (node (ref "J2") (pin "4") (pinfunction "4_4") (pintype "bidirectional"))
      (node (ref "Q2") (pin "G") (pinfunction "G_G") (pintype "passive"))
    )
    (net (code "6") (name "D1_N") (class "Default")
      (node (ref "Q2") (pin "D") (pinfunction "D_D") (pintype "passive"))
      (node (ref "Q4") (pin "G") (pinfunction "G_G") (pintype "passive"))
      (node (ref "R3") (pin "1") (pinfunction "1_1") (pintype "passive"))
      (node (ref "R4") (pin "1") (pinfunction "1_1") (pintype "passive"))
      (node (ref "R46") (pin "1") (pinfunction "1_1") (pintype "passive"))
    )
    (net (code "7") (name "D2") (class "Default")
      (node (ref "J1") (pin "4") (pinfunction "4_4") (pintype "bidirectional"))
      (node (ref "J2") (pin "5") (pinfunction "5_5") (pintype "bidirectional"))
      (node (ref "Q6") (pin "G") (pinfunction "G_G") (pintype "passive"))
    )
    (net (code "8") (name "D2_N") (class "Default")
      (node (ref "Q6") (pin "D") (pinfunction "D_D") (pintype "passive"))
      (node (ref "Q8") (pin "G") (pinfunction "G_G") (pintype "passive"))
      (node (ref "R50") (pin "1") (pinfunction "1_1") (pintype "passive"))
      (node (ref "R6") (pin "1") (pinfunction "1_1") (pintype "passive"))
      (node (ref "R9") (pin "1") (pinfunction "1_1") (pintype "passive"))
    )
    (net (code "9") (name "D3") (class "Default")
      (node (ref "J1") (pin "5") (pinfunction "5_5") (pintype "bidirectional"))
      (node (ref "J2") (pin "6") (pinfunction "6_6") (pintype "bidirectional"))
      (node (ref "Q7") (pin "G") (pinfunction "G_G") (pintype "passive"))
    )
    (net (code "10") (name "D3_N") (class "Default")
      (node (ref "Q7") (pin "D") (pinfunction "D_D") (pintype "passive"))
      (node (ref "Q9") (pin "G") (pinfunction "G_G") (pintype "passive"))
      (node (ref "R10") (pin "1") (pinfunction "1_1") (pintype "passive"))
      (node (ref "R11") (pin "1") (pinfunction "1_1") (pintype "passive"))
      (node (ref "R54") (pin "1") (pinfunction "1_1") (pintype "passive"))
    )
    (net (code "11") (name "D4") (class "Default")
      (node (ref "J1") (pin "6") (pinfunction "6_6") (pintype "bidirectional"))
      (node (ref "J2") (pin "7") (pinfunction "7_7") (pintype "bidirectional"))
      (node (ref "Q14") (pin "G") (pinfunction "G_G") (pintype "passive"))
    )
    (net (code "12") (name "D4_N") (class "Default")
      (node (ref "Q10") (pin "G") (pinfunction "G_G") (pintype "passive"))
      (node (ref "Q14") (pin "D") (pinfunction "D_D") (pintype "passive"))
      (node (ref "R12") (pin "1") (pinfunction "1_1") (pintype "passive"))
      (node (ref "R13") (pin "1") (pinfunction "1_1") (pintype "passive"))
      (node (ref "R56") (pin "1") (pinfunction "1_1") (pintype "passive"))
    )
    (net (code "13") (name "D5") (class "Default")
      (node (ref "J1") (pin "7") (pinfunction "7_7") (pintype "bidirectional"))
      (node (ref "J2") (pin "8") (pinfunction "8_8") (pintype "bidirectional"))
      (node (ref "Q15") (pin "G") (pinfunction "G_G") (pintype "passive"))
    )
    (net (code "14") (name "D5_N") (class "Default")
      (node (ref "Q11") (pin "G") (pinfunction "G_G") (pintype "passive"))
      (node (ref "Q15") (pin "D") (pinfunction "D_D") (pintype "passive"))
      (node (ref "R14") (pin "1") (pinfunction "1_1") (pintype "passive"))
      (node (ref "R15") (pin "1") (pinfunction "1_1") (pintype "passive"))
      (node (ref "R58") (pin "1") (pinfunction "1_1") (pintype "passive"))
    )
    (net (code "15") (name "D6") (class "Default")
      (node (ref "J1") (pin "8") (pinfunction "8_8") (pintype "bidirectional"))
      (node (ref "J2") (pin "9") (pinfunction "9_9") (pintype "bidirectional"))
      (node (ref "Q16") (pin "G") (pinfunction "G_G") (pintype "passive"))
    )
    (net (code "16") (name "D6_N") (class "Default")
      (node (ref "Q12") (pin "G") (pinfunction "G_G") (pintype "passive"))
      (node (ref "Q16") (pin "D") (pinfunction "D_D") (pintype "passive"))
      (node (ref "R16") (pin "1") (pinfunction "1_1") (pintype "passive"))
      (node (ref "R17") (pin "1") (pinfunction "1_1") (pintype "passive"))
      (node (ref "R60") (pin "1") (pinfunction "1_1") (pintype "passive"))
    )
    (net (code "17") (name "D7") (class "Default")
      (node (ref "J1") (pin "9") (pinfunction "9_9") (pintype "bidirectional"))
      (node (ref "J2") (pin "12") (pinfunction "12_12") (pintype "bidirectional"))
      (node (ref "Q17") (pin "G") (pinfunction "G_G") (pintype "passive"))
    )
    (net (code "18") (name "D7_N") (class "Default")
      (node (ref "Q13") (pin "G") (pinfunction "G_G") (pintype "passive"))
      (node (ref "Q17") (pin "D") (pinfunction "D_D") (pintype "passive"))
      (node (ref "R18") (pin "1") (pinfunction "1_1") (pintype "passive"))
      (node (ref "R19") (pin "1") (pinfunction "1_1") (pintype "passive"))
      (node (ref "R62") (pin "1") (pinfunction "1_1") (pintype "passive"))
    )
    (net (code "19") (name "D8") (class "Default")
      (node (ref "J1") (pin "12") (pinfunction "12_12") (pintype "bidirectional"))
      (node (ref "J2") (pin "13") (pinfunction "13_13") (pintype "bidirectional"))
      (node (ref "Q20") (pin "G") (pinfunction "G_G") (pintype "passive"))
    )
    (net (code "20") (name "D8_N") (class "Default")
      (node (ref "Q20") (pin "D") (pinfunction "D_D") (pintype "passive"))
      (node (ref "Q22") (pin "G") (pinfunction "G_G") (pintype "passive"))
      (node (ref "R21") (pin "1") (pinfunction "1_1") (pintype "passive"))
      (node (ref "R22") (pin "1") (pinfunction "1_1") (pintype "passive"))
      (node (ref "R39") (pin "1") (pinfunction "1_1") (pintype "passive"))
    )
    (net (code "21") (name "D9") (class "Default")
      (node (ref "J1") (pin "13") (pinfunction "13_13") (pintype "bidirectional"))
      (node (ref "J2") (pin "14") (pinfunction "14_14") (pintype "bidirectional"))
      (node (ref "Q21") (pin "G") (pinfunction "G_G") (pintype "passive"))
    )
    (net (code "22") (name "D9_N") (class "Default")
      (node (ref "Q21") (pin "D") (pinfunction "D_D") (pintype "passive"))
      (node (ref "Q23") (pin "G") (pinfunction "G_G") (pintype "passive"))
      (node (ref "R23") (pin "1") (pinfunction "1_1") (pintype "passive"))
      (node (ref "R24") (pin "1") (pinfunction "1_1") (pintype "passive"))
      (node (ref "R41") (pin "1") (pinfunction "1_1") (pintype "passive"))
    )
    (net (code "23") (name "D10") (class "Default")
      (node (ref "J1") (pin "14") (pinfunction "14_14") (pintype "bidirectional"))
      (node (ref "J2") (pin "15") (pinfunction "15_15") (pintype "bidirectional"))
      (node (ref "Q24") (pin "G") (pinfunction "G_G") (pintype "passive"))
    )
    (net (code "24") (name "D10_N") (class "Default")
      (node (ref "Q24") (pin "D") (pinfunction "D_D") (pintype "passive"))
      (node (ref "Q26") (pin "G") (pinfunction "G_G") (pintype "passive"))
      (node (ref "R26") (pin "1") (pinfunction "1_1") (pintype "passive"))
      (node (ref "R27") (pin "1") (pinfunction "1_1") (pintype "passive"))
      (node (ref "R43") (pin "1") (pinfunction "1_1") (pintype "passive"))
    )
    (net (code "25") (name "D11") (class "Default")
      (node (ref "J1") (pin "15") (pinfunction "15_15") (pintype "bidirectional"))
      (node (ref "J2") (pin "16") (pinfunction "16_16") (pintype "bidirectional"))
      (node (ref "Q25") (pin "G") (pinfunction "G_G") (pintype "passive"))
    )
    (net (code "26") (name "D11_N") (class "Default")
      (node (ref "Q25") (pin "D") (pinfunction "D_D") (pintype "passive"))
      (node (ref "Q27") (pin "G") (pinfunction "G_G") (pintype "passive"))
      (node (ref "R28") (pin "1") (pinfunction "1_1") (pintype "passive"))
      (node (ref "R29") (pin "1") (pinfunction "1_1") (pintype "passive"))
      (node (ref "R45") (pin "1") (pinfunction "1_1") (pintype "passive"))
    )
    (net (code "27") (name "D12") (class "Default")
      (node (ref "J1") (pin "16") (pinfunction "16_16") (pintype "bidirectional"))
      (node (ref "J2") (pin "17") (pinfunction "17_17") (pintype "bidirectional"))
      (node (ref "Q32") (pin "G") (pinfunction "G_G") (pintype "passive"))
    )
    (net (code "28") (name "D12_N") (class "Default")
      (node (ref "Q28") (pin "G") (pinfunction "G_G") (pintype "passive"))
      (node (ref "Q32") (pin "D") (pinfunction "D_D") (pintype "passive"))
      (node (ref "R30") (pin "1") (pinfunction "1_1") (pintype "passive"))
      (node (ref "R31") (pin "1") (pinfunction "1_1") (pintype "passive"))
      (node (ref "R47") (pin "1") (pinfunction "1_1") (pintype "passive"))
    )
    (net (code "29") (name "D13") (class "Default")
      (node (ref "J1") (pin "17") (pinfunction "17_17") (pintype "bidirectional"))
      (node (ref "J2") (pin "18") (pinfunction "18_18") (pintype "bidirectional"))
      (node (ref "Q33") (pin "G") (pinfunction "G_G") (pintype "passive"))
    )
    (net (code "30") (name "D13_N") (class "Default")
      (node (ref "Q29") (pin "G") (pinfunction "G_G") (pintype "passive"))
      (node (ref "Q33") (pin "D") (pinfunction "D_D") (pintype "passive"))
      (node (ref "R32") (pin "1") (pinfunction "1_1") (pintype "passive"))
      (node (ref "R33") (pin "1") (pinfunction "1_1") (pintype "passive"))
      (node (ref "R49") (pin "1") (pinfunction "1_1") (pintype "passive"))
    )
    (net (code "31") (name "D14") (class "Default")
      (node (ref "J1") (pin "18") (pinfunction "18_18") (pintype "bidirectional"))
      (node (ref "J2") (pin "19") (pinfunction "19_19") (pintype "bidirectional"))
      (node (ref "J3") (pin "9") (pinfunction "9_9") (pintype "passive"))
      (node (ref "Q34") (pin "G") (pinfunction "G_G") (pintype "passive"))
    )
    (net (code "32") (name "D14_N") (class "Default")
      (node (ref "Q30") (pin "G") (pinfunction "G_G") (pintype "passive"))
      (node (ref "Q34") (pin "D") (pinfunction "D_D") (pintype "passive"))
      (node (ref "R34") (pin "1") (pinfunction "1_1") (pintype "passive"))
      (node (ref "R35") (pin "1") (pinfunction "1_1") (pintype "passive"))
      (node (ref "R51") (pin "1") (pinfunction "1_1") (pintype "passive"))
    )
    (net (code "33") (name "D15") (class "Default")
      (node (ref "J1") (pin "19") (pinfunction "19_19") (pintype "bidirectional"))
      (node (ref "J3") (pin "10") (pinfunction "10_10") (pintype "passive"))
      (node (ref "J3") (pin "3") (pinfunction "3_3") (pintype "passive"))
      (node (ref "J3") (pin "7") (pinfunction "7_7") (pintype "passive"))
      (node (ref "Q35") (pin "G") (pinfunction "G_G") (pintype "passive"))
    )
    (net (code "34") (name "D15_N") (class "Default")
      (node (ref "Q35") (pin "D") (pinfunction "D_D") (pintype "passive"))
      (node (ref "R36") (pin "1") (pinfunction "1_1") (pintype "passive"))
      (node (ref "R37") (pin "1") (pinfunction "1_1") (pintype "passive"))
    )
    (net (code "35") (name "GND") (class "Default")
      (node (ref "C1") (pin "2") (pinfunction "2_2") (pintype "passive"))
      (node (ref "C2") (pin "2") (pinfunction "2_2") (pintype "passive"))
      (node (ref "J1") (pin "1") (pinfunction "1_1") (pintype "bidirectional"))
      (node (ref "J1") (pin "10") (pinfunction "10_10") (pintype "bidirectional"))
      (node (ref "J1") (pin "11") (pinfunction "11_11") (pintype "bidirectional"))
      (node (ref "J1") (pin "20") (pinfunction "20_20") (pintype "bidirectional"))
      (node (ref "J2") (pin "1") (pinfunction "1_1") (pintype "bidirectional"))
      (node (ref "J2") (pin "10") (pinfunction "10_10") (pintype "bidirectional"))
      (node (ref "J2") (pin "11") (pinfunction "11_11") (pintype "bidirectional"))
      (node (ref "J2") (pin "20") (pinfunction "20_20") (pintype "bidirectional"))
      (node (ref "Q1") (pin "S") (pinfunction "S_S") (pintype "passive"))
      (node (ref "Q13") (pin "S") (pinfunction "S_S") (pintype "passive"))
      (node (ref "Q14") (pin "S") (pinfunction "S_S") (pintype "passive"))
      (node (ref "Q15") (pin "S") (pinfunction "S_S") (pintype "passive"))
      (node (ref "Q16") (pin "S") (pinfunction "S_S") (pintype "passive"))
      (node (ref "Q17") (pin "S") (pinfunction "S_S") (pintype "passive"))
      (node (ref "Q18") (pin "S") (pinfunction "S_S") (pintype "passive"))
      (node (ref "Q19") (pin "S") (pinfunction "S_S") (pintype "passive"))
      (node (ref "Q2") (pin "S") (pinfunction "S_S") (pintype "passive"))
      (node (ref "Q20") (pin "S") (pinfunction "S_S") (pintype "passive"))
      (node (ref "Q21") (pin "S") (pinfunction "S_S") (pintype "passive"))
      (node (ref "Q24") (pin "S") (pinfunction "S_S") (pintype "passive"))
      (node (ref "Q25") (pin "S") (pinfunction "S_S") (pintype "passive"))
      (node (ref "Q30") (pin "S") (pinfunction "S_S") (pintype "passive"))
      (node (ref "Q31") (pin "S") (pinfunction "S_S") (pintype "passive"))
      (node (ref "Q32") (pin "S") (pinfunction "S_S") (pintype "passive"))
      (node (ref "Q33") (pin "S") (pinfunction "S_S") (pintype "passive"))
      (node (ref "Q34") (pin "S") (pinfunction "S_S") (pintype "passive"))
      (node (ref "Q35") (pin "S") (pinfunction "S_S") (pintype "passive"))
      (node (ref "Q36") (pin "S") (pinfunction "S_S") (pintype "passive"))
      (node (ref "Q37") (pin "S") (pinfunction "S_S") (pintype "passive"))
      (node (ref "Q5") (pin "S") (pinfunction "S_S") (pintype "passive"))
      (node (ref "Q6") (pin "S") (pinfunction "S_S") (pintype "passive"))
      (node (ref "Q7") (pin "S") (pinfunction "S_S") (pintype "passive"))
      (node (ref "TP1") (pin "P$1") (pinfunction "P$1_P$1") (pintype "bidirectional"))
    )
    (net (code "36") (name "LSB_OR") (class "Default")
      (node (ref "Q3") (pin "D") (pinfunction "D_D") (pintype "passive"))
      (node (ref "Q5") (pin "G") (pinfunction "G_G") (pintype "passive"))
      (node (ref "R5") (pin "1") (pinfunction "1_1") (pintype "passive"))
    )
    (net (code "37") (name "MSB_OR") (class "Default")
      (node (ref "Q18") (pin "G") (pinfunction "G_G") (pintype "passive"))
      (node (ref "Q22") (pin "D") (pinfunction "D_D") (pintype "passive"))
      (node (ref "R25") (pin "1") (pinfunction "1_1") (pintype "passive"))
    )
    (net (code "38") (name "N$18") (class "Default")
      (node (ref "J3") (pin "5") (pinfunction "5_5") (pintype "passive"))
      (node (ref "TP8") (pin "P$1") (pinfunction "P$1_P$1") (pintype "bidirectional"))
    )
    (net (code "39") (name "N$58") (class "Default")
      (node (ref "J3") (pin "8") (pinfunction "8_8") (pintype "passive"))
      (node (ref "TP7") (pin "P$1") (pinfunction "P$1_P$1") (pintype "bidirectional"))
    )
    (net (code "40") (name "Net-(D1-C)") (class "Default")
      (node (ref "D1") (pin "K") (pinfunction "C_K") (pintype "passive"))
      (node (ref "R2") (pin "2") (pinfunction "2_2") (pintype "passive"))
    )
    (net (code "41") (name "Net-(D2-C)") (class "Default")
      (node (ref "D2") (pin "K") (pinfunction "C_K") (pintype "passive"))
      (node (ref "R4") (pin "2") (pinfunction "2_2") (pintype "passive"))
    )
    (net (code "42") (name "Net-(D3-C)") (class "Default")
      (node (ref "D3") (pin "K") (pinfunction "C_K") (pintype "passive"))
      (node (ref "R9") (pin "2") (pinfunction "2_2") (pintype "passive"))
    )
    (net (code "43") (name "Net-(D4-C)") (class "Default")
      (node (ref "D4") (pin "K") (pinfunction "C_K") (pintype "passive"))
      (node (ref "R8") (pin "2") (pinfunction "2_2") (pintype "passive"))
    )
    (net (code "44") (name "Net-(D5-C)") (class "Default")
      (node (ref "D5") (pin "K") (pinfunction "C_K") (pintype "passive"))
      (node (ref "R11") (pin "2") (pinfunction "2_2") (pintype "passive"))
    )
    (net (code "45") (name "Net-(D6-C)") (class "Default")
      (node (ref "D6") (pin "K") (pinfunction "C_K") (pintype "passive"))
      (node (ref "R13") (pin "2") (pinfunction "2_2") (pintype "passive"))
    )
    (net (code "46") (name "Net-(D7-C)") (class "Default")
      (node (ref "D7") (pin "K") (pinfunction "C_K") (pintype "passive"))
      (node (ref "R15") (pin "2") (pinfunction "2_2") (pintype "passive"))
    )
    (net (code "47") (name "Net-(D8-C)") (class "Default")
      (node (ref "D8") (pin "K") (pinfunction "C_K") (pintype "passive"))
      (node (ref "R17") (pin "2") (pinfunction "2_2") (pintype "passive"))
    )
    (net (code "48") (name "Net-(D9-C)") (class "Default")
      (node (ref "D9") (pin "K") (pinfunction "C_K") (pintype "passive"))
      (node (ref "R19") (pin "2") (pinfunction "2_2") (pintype "passive"))
    )
    (net (code "49") (name "Net-(D10-C)") (class "Default")
      (node (ref "D10") (pin "K") (pinfunction "C_K") (pintype "passive"))
      (node (ref "R22") (pin "2") (pinfunction "2_2") (pintype "passive"))
    )
    (net (code "50") (name "Net-(D11-C)") (class "Default")
      (node (ref "D11") (pin "K") (pinfunction "C_K") (pintype "passive"))
      (node (ref "R24") (pin "2") (pinfunction "2_2") (pintype "passive"))
    )
    (net (code "51") (name "Net-(D12-C)") (class "Default")
      (node (ref "D12") (pin "K") (pinfunction "C_K") (pintype "passive"))
      (node (ref "R27") (pin "2") (pinfunction "2_2") (pintype "passive"))
    )
    (net (code "52") (name "Net-(D13-C)") (class "Default")
      (node (ref "D13") (pin "K") (pinfunction "C_K") (pintype "passive"))
      (node (ref "R29") (pin "2") (pinfunction "2_2") (pintype "passive"))
    )
    (net (code "53") (name "Net-(D14-C)") (class "Default")
      (node (ref "D14") (pin "K") (pinfunction "C_K") (pintype "passive"))
      (node (ref "R31") (pin "2") (pinfunction "2_2") (pintype "passive"))
    )
    (net (code "54") (name "Net-(D15-C)") (class "Default")
      (node (ref "D15") (pin "K") (pinfunction "C_K") (pintype "passive"))
      (node (ref "R33") (pin "2") (pinfunction "2_2") (pintype "passive"))
    )
    (net (code "55") (name "Net-(D16-C)") (class "Default")
      (node (ref "D16") (pin "K") (pinfunction "C_K") (pintype "passive"))
      (node (ref "R35") (pin "2") (pinfunction "2_2") (pintype "passive"))
    )
    (net (code "56") (name "Net-(D17-C)") (class "Default")
      (node (ref "D17") (pin "K") (pinfunction "C_K") (pintype "passive"))
      (node (ref "R37") (pin "2") (pinfunction "2_2") (pintype "passive"))
    )
    (net (code "57") (name "Net-(D18-C)") (class "Default")
      (node (ref "D18") (pin "K") (pinfunction "C_K") (pintype "passive"))
      (node (ref "R38") (pin "2") (pinfunction "2_2") (pintype "passive"))
    )
    (net (code "58") (name "Net-(D19-C)") (class "Default")
      (node (ref "D19") (pin "K") (pinfunction "C_K") (pintype "passive"))
      (node (ref "R39") (pin "2") (pinfunction "2_2") (pintype "passive"))
    )
    (net (code "59") (name "Net-(D20-C)") (class "Default")
      (node (ref "D20") (pin "K") (pinfunction "C_K") (pintype "passive"))
      (node (ref "R41") (pin "2") (pinfunction "2_2") (pintype "passive"))
    )
    (net (code "60") (name "Net-(D21-C)") (class "Default")
      (node (ref "D21") (pin "K") (pinfunction "C_K") (pintype "passive"))
      (node (ref "R43") (pin "2") (pinfunction "2_2") (pintype "passive"))
    )
    (net (code "61") (name "Net-(D22-C)") (class "Default")
      (node (ref "D22") (pin "K") (pinfunction "C_K") (pintype "passive"))
      (node (ref "R45") (pin "2") (pinfunction "2_2") (pintype "passive"))
    )
    (net (code "62") (name "Net-(D23-C)") (class "Default")
      (node (ref "D23") (pin "K") (pinfunction "C_K") (pintype "passive"))
      (node (ref "R47") (pin "2") (pinfunction "2_2") (pintype "passive"))
    )
    (net (code "63") (name "Net-(D24-C)") (class "Default")
      (node (ref "D24") (pin "K") (pinfunction "C_K") (pintype "passive"))
      (node (ref "R49") (pin "2") (pinfunction "2_2") (pintype "passive"))
    )
    (net (code "64") (name "Net-(D25-C)") (class "Default")
      (node (ref "D25") (pin "K") (pinfunction "C_K") (pintype "passive"))
      (node (ref "R51") (pin "2") (pinfunction "2_2") (pintype "passive"))
    )
    (net (code "65") (name "Net-(D27-C)") (class "Default")
      (node (ref "D27") (pin "K") (pinfunction "C_K") (pintype "passive"))
      (node (ref "R42") (pin "2") (pinfunction "2_2") (pintype "passive"))
    )
    (net (code "66") (name "Net-(D28-C)") (class "Default")
      (node (ref "D28") (pin "K") (pinfunction "C_K") (pintype "passive"))
      (node (ref "R46") (pin "2") (pinfunction "2_2") (pintype "passive"))
    )
    (net (code "67") (name "Net-(D29-C)") (class "Default")
      (node (ref "D29") (pin "K") (pinfunction "C_K") (pintype "passive"))
      (node (ref "R50") (pin "2") (pinfunction "2_2") (pintype "passive"))
    )
    (net (code "68") (name "Net-(D30-C)") (class "Default")
      (node (ref "D30") (pin "K") (pinfunction "C_K") (pintype "passive"))
      (node (ref "R54") (pin "2") (pinfunction "2_2") (pintype "passive"))
    )
    (net (code "69") (name "Net-(D31-C)") (class "Default")
      (node (ref "D31") (pin "K") (pinfunction "C_K") (pintype "passive"))
      (node (ref "R56") (pin "2") (pinfunction "2_2") (pintype "passive"))
    )
    (net (code "70") (name "Net-(D32-C)") (class "Default")
      (node (ref "D32") (pin "K") (pinfunction "C_K") (pintype "passive"))
      (node (ref "R58") (pin "2") (pinfunction "2_2") (pintype "passive"))
    )
    (net (code "71") (name "Net-(D33-C)") (class "Default")
      (node (ref "D33") (pin "K") (pinfunction "C_K") (pintype "passive"))
      (node (ref "R60") (pin "2") (pinfunction "2_2") (pintype "passive"))
    )
    (net (code "72") (name "Net-(D34-C)") (class "Default")
      (node (ref "D34") (pin "K") (pinfunction "C_K") (pintype "passive"))
      (node (ref "R62") (pin "2") (pinfunction "2_2") (pintype "passive"))
    )
    (net (code "73") (name "Net-(D35-C)") (class "Default")
      (node (ref "D35") (pin "K") (pinfunction "C_K") (pintype "passive"))
      (node (ref "R44") (pin "2") (pinfunction "2_2") (pintype "passive"))
    )
    (net (code "74") (name "Net-(Q3-PadS)") (class "Default")
      (node (ref "Q3") (pin "S") (pinfunction "S_S") (pintype "passive"))
      (node (ref "Q4") (pin "D") (pinfunction "D_D") (pintype "passive"))
    )
    (net (code "75") (name "Net-(Q4-PadS)") (class "Default")
      (node (ref "Q4") (pin "S") (pinfunction "S_S") (pintype "passive"))
      (node (ref "Q8") (pin "D") (pinfunction "D_D") (pintype "passive"))
    )
    (net (code "76") (name "Net-(Q8-PadS)") (class "Default")
      (node (ref "Q8") (pin "S") (pinfunction "S_S") (pintype "passive"))
      (node (ref "Q9") (pin "D") (pinfunction "D_D") (pintype "passive"))
    )
    (net (code "77") (name "Net-(Q10-PadD)") (class "Default")
      (node (ref "Q10") (pin "D") (pinfunction "D_D") (pintype "passive"))
      (node (ref "Q9") (pin "S") (pinfunction "S_S") (pintype "passive"))
    )
    (net (code "78") (name "Net-(Q10-PadS)") (class "Default")
      (node (ref "Q10") (pin "S") (pinfunction "S_S") (pintype "passive"))
      (node (ref "Q11") (pin "D") (pinfunction "D_D") (pintype "passive"))
    )
    (net (code "79") (name "Net-(Q11-PadS)") (class "Default")
      (node (ref "Q11") (pin "S") (pinfunction "S_S") (pintype "passive"))
      (node (ref "Q12") (pin "D") (pinfunction "D_D") (pintype "passive"))
    )
    (net (code "80") (name "Net-(Q12-PadS)") (class "Default")
      (node (ref "Q12") (pin "S") (pinfunction "S_S") (pintype "passive"))
      (node (ref "Q13") (pin "D") (pinfunction "D_D") (pintype "passive"))
    )
    (net (code "81") (name "Net-(Q18-PadD)") (class "Default")
      (node (ref "Q18") (pin "D") (pinfunction "D_D") (pintype "passive"))
      (node (ref "Q19") (pin "G") (pinfunction "G_G") (pintype "passive"))
      (node (ref "Q31") (pin "D") (pinfunction "D_D") (pintype "passive"))
      (node (ref "Q5") (pin "D") (pinfunction "D_D") (pintype "passive"))
      (node (ref "R7") (pin "1") (pinfunction "1_1") (pintype "passive"))
      (node (ref "TP4") (pin "P$1") (pinfunction "P$1_P$1") (pintype "bidirectional"))
    )
    (net (code "82") (name "Net-(Q19-PadD)") (class "Default")
      (node (ref "Q19") (pin "D") (pinfunction "D_D") (pintype "passive"))
      (node (ref "R20") (pin "1") (pinfunction "1_1") (pintype "passive"))
      (node (ref "R8") (pin "1") (pinfunction "1_1") (pintype "passive"))
    )
    (net (code "83") (name "Net-(Q22-PadS)") (class "Default")
      (node (ref "Q22") (pin "S") (pinfunction "S_S") (pintype "passive"))
      (node (ref "Q23") (pin "D") (pinfunction "D_D") (pintype "passive"))
    )
    (net (code "84") (name "Net-(Q23-PadS)") (class "Default")
      (node (ref "Q23") (pin "S") (pinfunction "S_S") (pintype "passive"))
      (node (ref "Q26") (pin "D") (pinfunction "D_D") (pintype "passive"))
    )
    (net (code "85") (name "Net-(Q26-PadS)") (class "Default")
      (node (ref "Q26") (pin "S") (pinfunction "S_S") (pintype "passive"))
      (node (ref "Q27") (pin "D") (pinfunction "D_D") (pintype "passive"))
    )
    (net (code "86") (name "Net-(Q27-PadS)") (class "Default")
      (node (ref "Q27") (pin "S") (pinfunction "S_S") (pintype "passive"))
      (node (ref "Q28") (pin "D") (pinfunction "D_D") (pintype "passive"))
    )
    (net (code "87") (name "Net-(Q28-PadS)") (class "Default")
      (node (ref "Q28") (pin "S") (pinfunction "S_S") (pintype "passive"))
      (node (ref "Q29") (pin "D") (pinfunction "D_D") (pintype "passive"))
    )
    (net (code "88") (name "Net-(Q29-PadS)") (class "Default")
      (node (ref "Q29") (pin "S") (pinfunction "S_S") (pintype "passive"))
      (node (ref "Q30") (pin "D") (pinfunction "D_D") (pintype "passive"))
    )
    (net (code "89") (name "Net-(Q36-PadD)") (class "Default")
      (node (ref "Q36") (pin "D") (pinfunction "D_D") (pintype "passive"))
      (node (ref "R38") (pin "1") (pinfunction "1_1") (pintype "passive"))
    )
    (net (code "90") (name "RIGHT_0") (class "Default")
      (node (ref "J2") (pin "2") (pinfunction "2_2") (pintype "bidirectional"))
      (node (ref "J3") (pin "1") (pinfunction "1_1") (pintype "passive"))
      (node (ref "J3") (pin "12") (pinfunction "12_12") (pintype "passive"))
      (node (ref "J3") (pin "6") (pinfunction "6_6") (pintype "passive"))
      (node (ref "Q37") (pin "G") (pinfunction "G_G") (pintype "passive"))
    )
    (net (code "91") (name "RIGHT_0__N") (class "Default")
      (node (ref "Q37") (pin "D") (pinfunction "D_D") (pintype "passive"))
      (node (ref "R40") (pin "1") (pinfunction "1_1") (pintype "passive"))
      (node (ref "R42") (pin "1") (pinfunction "1_1") (pintype "passive"))
    )
    (net (code "92") (name "VARYING_BIT") (class "Default")
      (node (ref "J3") (pin "11") (pinfunction "11_11") (pintype "passive"))
      (node (ref "Q31") (pin "G") (pinfunction "G_G") (pintype "passive"))
    )
  )
)
